# EXTERNAL_FAN.net
KiCad netlist of a schematic drawn in Altium Designer
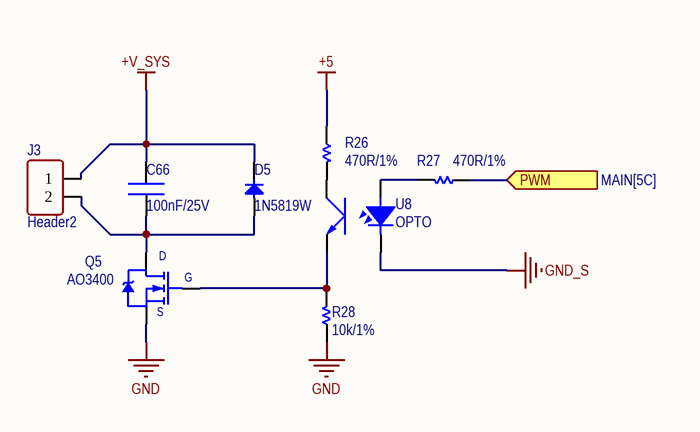
[diagram p0: EXTERNAL_FAN.SchDoc]

(export (version "E")
  (design (tool "Eeschema 10.0.6"))
  (components
    (comp (ref "C66")
      (value "100nF/25V")
      (footprint "CN-SMD-0603")
      (description "CAP CER 0.1UF 25V X7R 0603")
      (libsource (lib "Library") (part "CN"))
    )
    (comp (ref "D5")
      (value "1N5819W")
      (footprint "DIO-SMD-123")
      (description "DIODE SCHOTTKY 40V 1A SOD123FL")
      (fields (field (name "PUBLISHER") "Altium Limited"))
      (libsource (lib "Library") (part "Diode SMD"))
    )
    (comp (ref "J3")
      (value "Header2")
      (footprint "XH2.54-2-DIP")
      (description "Connector 2")
      (fields
        (field (name "MANUFACTURER") "Würth Elektronik eiSos GmbH")
        (field (name "PARTNO") "613002143121")
        (field (name "CREATED BY") "Karrer Zheng")
      )
      (libsource (lib "Library") (part "Header2"))
    )
    (comp (ref "Q5")
      (value "AO3400")
      (footprint "SOT23-123")
      (description "MOSFET N-CH 30V 5.7A SOT23-3L")
      (libsource (lib "Library") (part "AO3400"))
    )
    (comp (ref "R26")
      (value "470R/1%")
      (footprint "RES-SMD-0603")
      (description "RES 470 OHM 1% 1/10W 0603")
      (fields
        (field (name "MANUFACTURER") "Generic Components")
        (field (name "PUBLISHER") "Altium Hobart Technology Centre")
      )
      (libsource (lib "Library") (part "Res-SMD"))
    )
    (comp (ref "R27")
      (value "470R/1%")
      (footprint "RES-SMD-0603")
      (description "RES 470 OHM 1% 1/10W 0603")
      (fields
        (field (name "MANUFACTURER") "Generic Components")
        (field (name "PUBLISHER") "Altium Hobart Technology Centre")
      )
      (libsource (lib "Library") (part "Res-SMD"))
    )
    (comp (ref "R28")
      (value "10k/1%")
      (footprint "RES-SMD-0603")
      (description "RES SMD 10K OHM 1% 1/10W 0603")
      (fields
        (field (name "MANUFACTURER") "Generic Components")
        (field (name "PUBLISHER") "Altium Hobart Technology Centre")
      )
      (libsource (lib "Library") (part "Res-SMD"))
    )
    (comp (ref "U8")
      (value "OPTO")
      (footprint "EL3H7")
      (description "OPTOISO 3.75KV 1CH TRANS 4-SSOP")
      (libsource (lib "Library") (part "OPTO"))
    )
  )
  (nets
    (net (code "1") (name "+5") (class "Default")
      (node (ref "R26") (pin "1") (pinfunction "1_1") (pintype "passive"))
    )
    (net (code "2") (name "+V_SYS") (class "Default")
      (node (ref "C66") (pin "1") (pinfunction "1_1") (pintype "passive"))
      (node (ref "D5") (pin "2") (pinfunction "K_2") (pintype "passive"))
      (node (ref "J3") (pin "1") (pinfunction "1_1") (pintype "passive"))
    )
    (net (code "3") (name "/PWM") (class "Default")
      (node (ref "R27") (pin "1") (pinfunction "1_1") (pintype "passive"))
    )
    (net (code "4") (name "GND") (class "Default")
      (node (ref "Q5") (pin "3") (pinfunction "S_3") (pintype "passive"))
      (node (ref "R28") (pin "1") (pinfunction "1_1") (pintype "passive"))
    )
    (net (code "5") (name "GND_S") (class "Default")
      (node (ref "U8") (pin "K") (pinfunction "K_K") (pintype "passive"))
    )
    (net (code "6") (name "Net-(D5-A)") (class "Default")
      (node (ref "C66") (pin "2") (pinfunction "2_2") (pintype "passive"))
      (node (ref "D5") (pin "1") (pinfunction "A_1") (pintype "passive"))
      (node (ref "J3") (pin "2") (pinfunction "2_2") (pintype "passive"))
      (node (ref "Q5") (pin "2") (pinfunction "D_2") (pintype "passive"))
    )
    (net (code "7") (name "Net-(Q5-G)") (class "Default")
      (node (ref "Q5") (pin "1") (pinfunction "G_1") (pintype "passive"))
      (node (ref "R28") (pin "2") (pinfunction "2_2") (pintype "passive"))
      (node (ref "U8") (pin "E") (pinfunction "E_E") (pintype "passive"))
    )
    (net (code "8") (name "Net-(R26-Pad2)") (class "Default")
      (node (ref "R26") (pin "2") (pinfunction "2_2") (pintype "passive"))
      (node (ref "U8") (pin "C") (pinfunction "C_C") (pintype "passive"))
    )
    (net (code "9") (name "Net-(R27-Pad2)") (class "Default")
      (node (ref "R27") (pin "2") (pinfunction "2_2") (pintype "passive"))
      (node (ref "U8") (pin "A") (pinfunction "A_A") (pintype "passive"))
    )
  )
)
